# FE_channel.net
KiCad netlist of a schematic drawn in Altium Designer
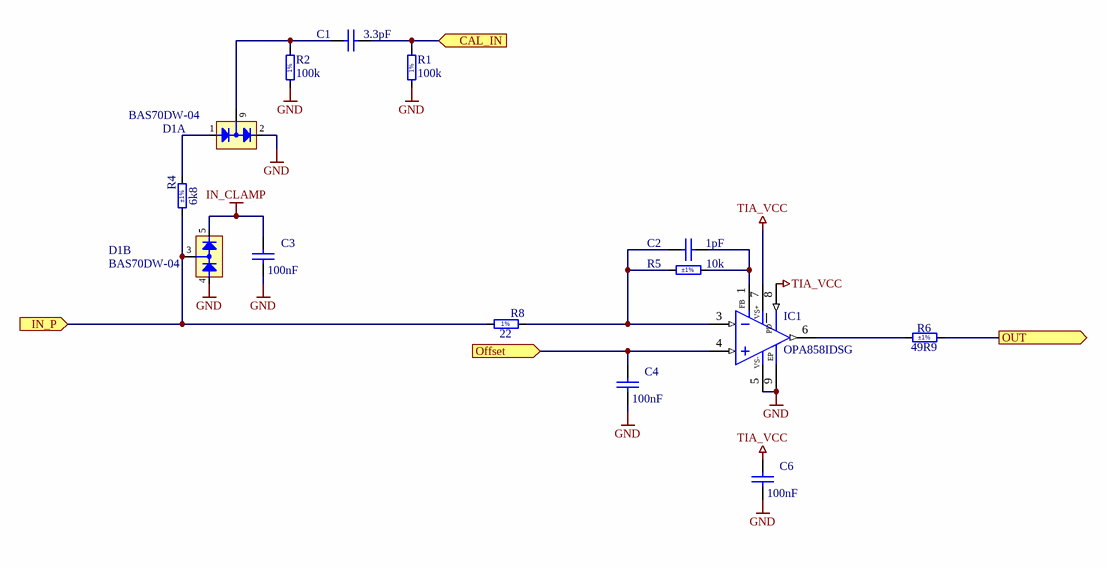
[diagram p0: FE_channel.SchDoc]

(export (version "E")
  (design (tool "Eeschema 10.0.6"))
  (components
    (comp (ref "C1")
      (value "3.3pF")
      (footprint "CAPC1005X55N")
      (description "Non-polarised capacitor")
      (fields
        (field (name "PART NUMBER") "CC0402_3.3PF_50V_0.25PF_C0G")
        (field (name "VOLTAGE") "50V")
        (field (name "AUTHOR") "CERN DEM JLC")
      )
      (libsource (lib "Capacitors") (part "Capacitor - non polarized"))
    )
    (comp (ref "C2")
      (value "1pF")
      (footprint "CAPC1005X55N")
      (description "Non-polarised capacitor")
      (fields
        (field (name "PART NUMBER") "CC0402_1PF_50V_0.25PF_C0G")
        (field (name "VOLTAGE") "50V")
        (field (name "AUTHOR") "CERN DEM JLC")
      )
      (libsource (lib "Capacitors") (part "Capacitor - non polarized"))
    )
    (comp (ref "C3")
      (value "100nF")
      (footprint "CAPC0603X33N")
      (description "Non-polarised capacitor")
      (fields
        (field (name "PART NUMBER") "CC0201_100NF_6.3V_10%_X5R")
        (field (name "VOLTAGE") "6.3V")
        (field (name "AUTHOR") "CERN DEM JLC")
      )
      (libsource (lib "Capacitors") (part "Capacitor - non polarized"))
    )
    (comp (ref "C4")
      (value "100nF")
      (footprint "CAPC0603X33N")
      (description "Non-polarised capacitor")
      (fields
        (field (name "PART NUMBER") "CC0201_100NF_6.3V_10%_X5R")
        (field (name "VOLTAGE") "6.3V")
        (field (name "AUTHOR") "CERN DEM JLC")
      )
      (libsource (lib "Capacitors") (part "Capacitor - non polarized"))
    )
    (comp (ref "C6")
      (value "100nF")
      (footprint "CAPC0603X33N")
      (description "Non-polarised capacitor")
      (fields
        (field (name "PART NUMBER") "CC0201_100NF_6.3V_10%_X5R")
        (field (name "VOLTAGE") "6.3V")
        (field (name "AUTHOR") "CERN DEM JLC")
      )
      (libsource (lib "Capacitors") (part "Capacitor - non polarized"))
    )
    (comp (ref "D1")
      (value "BAS70DW-04")
      (footprint "SOT65P210X110-6N")
      (description "70 V 70 mA Surface Mount Schottky Barrier Diode Arrays")
      (fields (field (name "VOLTAGE") "70V") (field (name "POWER") "70mA") (field (name "AUTHOR") "GK"))
      (libsource (lib "Diodes") (part "D_BAS70DW-04"))
    )
    (comp (ref "IC1")
      (value "OPA858IDSG")
      (footprint "TEXAS_DSG0008A")
      (description "5.5-GHz Gain Bandwidth Product, Gain of 7 V/V Stable, FET Input Amplifier")
      (fields (field (name "MANUFACTURER") "TEXAS INSTRUMENTS") (field (name "AUTHOR") "CERN DEM HF"))
      (libsource (lib "ICs And Semiconductors") (part "OPA858"))
    )
    (comp (ref "R1")
      (value "100k")
      (footprint "RESC1005X40N")
      (description "Resistor - 1%")
      (fields
        (field (name "PART NUMBER") "R0402_100K_1%_0.0625W_100PPM")
        (field (name "POWER") "0.0625W")
        (field (name "AUTHOR") "CERN DEM JLC")
      )
      (libsource (lib "Resistors") (part "Resistor - 1%"))
    )
    (comp (ref "R2")
      (value "100k")
      (footprint "RESC1005X40N")
      (description "Resistor - 1%")
      (fields
        (field (name "PART NUMBER") "R0402_100K_1%_0.0625W_100PPM")
        (field (name "POWER") "0.0625W")
        (field (name "AUTHOR") "CERN DEM JLC")
      )
      (libsource (lib "Resistors") (part "Resistor - 1%"))
    )
    (comp (ref "R4")
      (value "6k8")
      (footprint "RESC1005X40N")
      (description "Resistor - 1%")
      (fields
        (field (name "TOLERANCE") "±1%")
        (field (name "PART NUMBER") "R0402_6K8_1%_0.0625W_100PPM")
        (field (name "POWER") "0.0625W")
        (field (name "AUTHOR") "CERN DEM JLC")
      )
      (libsource (lib "Resistors") (part "Resistor - 1%"))
    )
    (comp (ref "R5")
      (value "10k")
      (footprint "RESC1005X40N")
      (description "Resistor - 1%")
      (fields
        (field (name "TOLERANCE") "±1%")
        (field (name "PART NUMBER") "R0402_10K_1%_0.0625W_100PPM")
        (field (name "POWER") "0.0625W")
        (field (name "AUTHOR") "CERN DEM JLC")
      )
      (libsource (lib "Resistors") (part "Resistor - 1%"))
    )
    (comp (ref "R6")
      (value "49R9")
      (footprint "RESC0603X28N")
      (description "Resistor - 1%")
      (fields
        (field (name "TOLERANCE") "±1%")
        (field (name "PART NUMBER") "R0201_49R9_1%_0.05W_200PPM")
        (field (name "POWER") "0.05W")
        (field (name "AUTHOR") "CERN DEM BC")
      )
      (libsource (lib "Resistors") (part "Resistor - 1%"))
    )
    (comp (ref "R8")
      (value "22")
      (footprint "RESC1005X40N")
      (description "Resistor - 1%")
      (fields
        (field (name "PART NUMBER") "R0402_22R_1%_0.0625W_100PPM")
        (field (name "POWER") "0.0625W")
        (field (name "AUTHOR") "CERN DEM JLC")
      )
      (libsource (lib "Resistors") (part "Resistor - 1%"))
    )
  )
  (nets
    (net (code "1") (name "/CAL_IN") (class "Default")
      (node (ref "C1") (pin "2") (pinfunction "2_2") (pintype "passive"))
      (node (ref "R1") (pin "2") (pinfunction "2_2") (pintype "passive"))
    )
    (net (code "2") (name "/IN_P") (class "Default")
      (node (ref "D1") (pin "3") (pinfunction "C3A4_3") (pintype "passive"))
      (node (ref "R4") (pin "1") (pinfunction "1_1") (pintype "passive"))
      (node (ref "R8") (pin "1") (pinfunction "1_1") (pintype "passive"))
    )
    (net (code "3") (name "/OUT") (class "Default")
      (node (ref "R6") (pin "2") (pinfunction "2_2") (pintype "passive"))
    )
    (net (code "4") (name "/Offset") (class "Default")
      (node (ref "C4") (pin "2") (pinfunction "2_2") (pintype "passive"))
      (node (ref "IC1") (pin "4") (pinfunction "IN+_4") (pintype "input"))
    )
    (net (code "5") (name "GND") (class "Default")
      (node (ref "C3") (pin "1") (pinfunction "1_1") (pintype "passive"))
      (node (ref "C4") (pin "1") (pinfunction "1_1") (pintype "passive"))
      (node (ref "C6") (pin "1") (pinfunction "1_1") (pintype "passive"))
      (node (ref "D1") (pin "2") (pinfunction "C2_2") (pintype "passive"))
      (node (ref "D1") (pin "4") (pinfunction "A3_4") (pintype "passive"))
      (node (ref "IC1") (pin "5") (pinfunction "VS-_5") (pintype "power_in"))
      (node (ref "IC1") (pin "9") (pinfunction "EP_9") (pintype "power_in"))
      (node (ref "R1") (pin "1") (pinfunction "1_1") (pintype "passive"))
      (node (ref "R2") (pin "1") (pinfunction "1_1") (pintype "passive"))
    )
    (net (code "6") (name "IN_CLAMP") (class "Default")
      (node (ref "C3") (pin "2") (pinfunction "2_2") (pintype "passive"))
      (node (ref "D1") (pin "5") (pinfunction "C4_5") (pintype "passive"))
    )
    (net (code "7") (name "Net-(D1A-A)") (class "Default")
      (node (ref "D1") (pin "1") (pinfunction "A_1") (pintype "passive"))
      (node (ref "R4") (pin "2") (pinfunction "2_2") (pintype "passive"))
    )
    (net (code "8") (name "Net-(D1A-C1A2)") (class "Default")
      (node (ref "C1") (pin "1") (pinfunction "1_1") (pintype "passive"))
      (node (ref "D1") (pin "6") (pinfunction "C1A2_6") (pintype "passive"))
      (node (ref "R2") (pin "2") (pinfunction "2_2") (pintype "passive"))
    )
    (net (code "9") (name "Net-(IC1-FB)") (class "Default")
      (node (ref "C2") (pin "2") (pinfunction "2_2") (pintype "passive"))
      (node (ref "IC1") (pin "1") (pinfunction "FB_1") (pintype "passive"))
      (node (ref "R5") (pin "2") (pinfunction "2_2") (pintype "passive"))
    )
    (net (code "10") (name "Net-(IC1-IN-)") (class "Default")
      (node (ref "C2") (pin "1") (pinfunction "1_1") (pintype "passive"))
      (node (ref "IC1") (pin "3") (pinfunction "IN-_3") (pintype "input"))
      (node (ref "R5") (pin "1") (pinfunction "1_1") (pintype "passive"))
      (node (ref "R8") (pin "2") (pinfunction "2_2") (pintype "passive"))
    )
    (net (code "11") (name "Net-(IC1-OUT)") (class "Default")
      (node (ref "IC1") (pin "6") (pinfunction "OUT_6") (pintype "output"))
      (node (ref "R6") (pin "1") (pinfunction "1_1") (pintype "passive"))
    )
    (net (code "12") (name "TIA_VCC") (class "Default")
      (node (ref "C6") (pin "2") (pinfunction "2_2") (pintype "passive"))
      (node (ref "IC1") (pin "7") (pinfunction "VS+_7") (pintype "power_in"))
      (node (ref "IC1") (pin "8") (pinfunction "/P/D_8") (pintype "input"))
    )
  )
)
